# Power_To_Board.net
KiCad netlist of a schematic drawn in Altium Designer
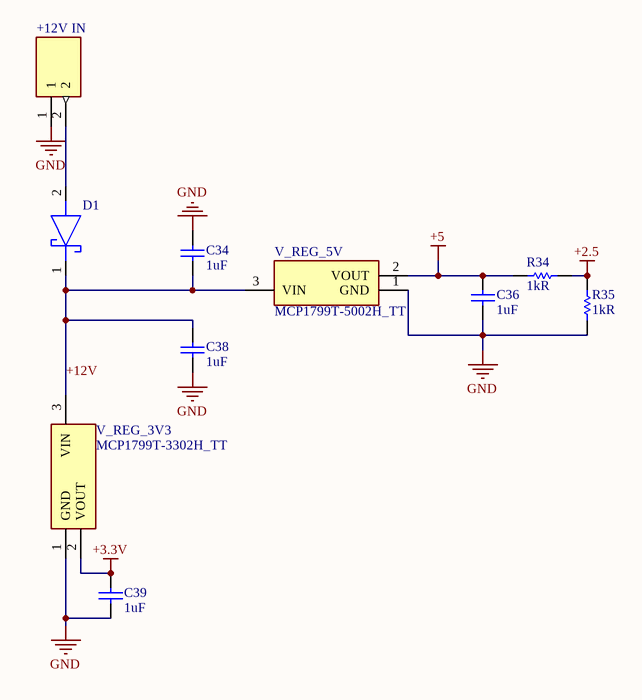
[diagram p0: Power To Board.SchDoc]

(export (version "E")
  (design (tool "Eeschema 10.0.6"))
  (components
    (comp (ref "+12V IN")
      (value "39773-0002")
      (footprint "SamacSys:397730002")
      (description "Connector")
      (libsource (lib "SamacSys") (part "39773-0002"))
    )
    (comp (ref "C34")
      (value "1uF")
      (footprint "CAPC1608X90X35LL15T15")
      (fields (field (name "MANUFACTURER") "Kemet") (field (name "PART NUMBER") "C0603C105K4RACTU"))
      (libsource (lib "Altium Content Vault") (part "CAP"))
    )
    (comp (ref "C36")
      (value "1uF")
      (footprint "CAPC1608X90X35LL15T15")
      (fields (field (name "MANUFACTURER") "Kemet") (field (name "PART NUMBER") "C0603C105K4RACTU"))
      (libsource (lib "Altium Content Vault") (part "CAP"))
    )
    (comp (ref "C38")
      (value "1uF")
      (footprint "CAPC1608X90X35LL15T15")
      (fields (field (name "MANUFACTURER") "Kemet") (field (name "PART NUMBER") "C0603C105K4RACTU"))
      (libsource (lib "Altium Content Vault") (part "CAP"))
    )
    (comp (ref "C39")
      (value "1uF")
      (footprint "CAPC1608X90X35LL15T15")
      (fields (field (name "MANUFACTURER") "Kemet") (field (name "PART NUMBER") "C0603C105K4RACTU"))
      (libsource (lib "Altium Content Vault") (part "CAP"))
    )
    (comp (ref "D1")
      (value "NSR20F20NXT5G")
      (footprint "SamacSys:NSR20F20NXT5G")
      (description "Schottky Diode")
      (libsource (lib "SamacSys") (part "NSR20F20NXT5G"))
    )
    (comp (ref "R34")
      (value "1kR")
      (footprint "RESC1608X55X30LL15T15")
      (fields (field (name "PART NUMBER") "ERJ-3EKF1001V") (field (name "MANUFACTURER") "Panasonic"))
      (libsource (lib "Altium Content Vault") (part "RES"))
    )
    (comp (ref "R35")
      (value "1kR")
      (footprint "RESC1608X55X30LL15T15")
      (fields (field (name "PART NUMBER") "ERJ-3EKF1001V") (field (name "MANUFACTURER") "Panasonic"))
      (libsource (lib "Altium Content Vault") (part "RES"))
    )
    (comp (ref "V_REG_3V3")
      (value "MCP1799T-3302H_TT")
      (footprint "SamacSys:SOT95P237X112-3N")
      (description "Power Supply")
      (fields (field (name "MANUFACTURER_PART_NUMBER") "MCP1799T-3302H/TT"))
      (libsource (lib "SamacSys") (part "MCP1799T-3302H_TT"))
    )
    (comp (ref "V_REG_5V")
      (value "MCP1799T-5002H_TT")
      (footprint "SamacSys:SOT95P237X112-3N")
      (description "Integrated Circuit")
      (fields (field (name "MANUFACTURER_PART_NUMBER") "MCP1799T-5002H/TT"))
      (libsource (lib "SamacSys") (part "MCP1799T-5002H_TT"))
    )
  )
  (nets
    (net (code "1") (name "+2.5") (class "Default")
      (node (ref "R34") (pin "1") (pinfunction "1_1") (pintype "passive"))
      (node (ref "R35") (pin "1") (pinfunction "1_1") (pintype "passive"))
    )
    (net (code "2") (name "+3.3V") (class "Default")
      (node (ref "C39") (pin "2") (pinfunction "2_2") (pintype "passive"))
      (node (ref "V_REG_3V3") (pin "2") (pinfunction "VOUT_2") (pintype "passive"))
    )
    (net (code "3") (name "+5") (class "Default")
      (node (ref "C36") (pin "2") (pinfunction "2_2") (pintype "passive"))
      (node (ref "R34") (pin "2") (pinfunction "2_2") (pintype "passive"))
      (node (ref "V_REG_5V") (pin "2") (pinfunction "VOUT_2") (pintype "power_in"))
    )
    (net (code "4") (name "/+12V") (class "Default")
      (node (ref "C34") (pin "1") (pinfunction "1_1") (pintype "passive"))
      (node (ref "C38") (pin "2") (pinfunction "2_2") (pintype "passive"))
      (node (ref "D1") (pin "1") (pinfunction "K_1") (pintype "passive"))
      (node (ref "V_REG_3V3") (pin "3") (pinfunction "VIN_3") (pintype "passive"))
      (node (ref "V_REG_5V") (pin "3") (pinfunction "VIN_3") (pintype "passive"))
    )
    (net (code "5") (name "GND") (class "Default")
      (node (ref "+12V IN") (pin "1") (pinfunction "1_1") (pintype "passive"))
      (node (ref "C34") (pin "2") (pinfunction "2_2") (pintype "passive"))
      (node (ref "C36") (pin "1") (pinfunction "1_1") (pintype "passive"))
      (node (ref "C38") (pin "1") (pinfunction "1_1") (pintype "passive"))
      (node (ref "C39") (pin "1") (pinfunction "1_1") (pintype "passive"))
      (node (ref "R35") (pin "2") (pinfunction "2_2") (pintype "passive"))
      (node (ref "V_REG_3V3") (pin "1") (pinfunction "GND_1") (pintype "passive"))
      (node (ref "V_REG_5V") (pin "1") (pinfunction "GND_1") (pintype "passive"))
    )
    (net (code "6") (name "Net-(D1-A)") (class "Default")
      (node (ref "+12V IN") (pin "2") (pinfunction "2_2") (pintype "output"))
      (node (ref "D1") (pin "2") (pinfunction "A_2") (pintype "passive"))
    )
  )
)
